# USB_hub.net
KiCad netlist of a schematic drawn in Altium Designer
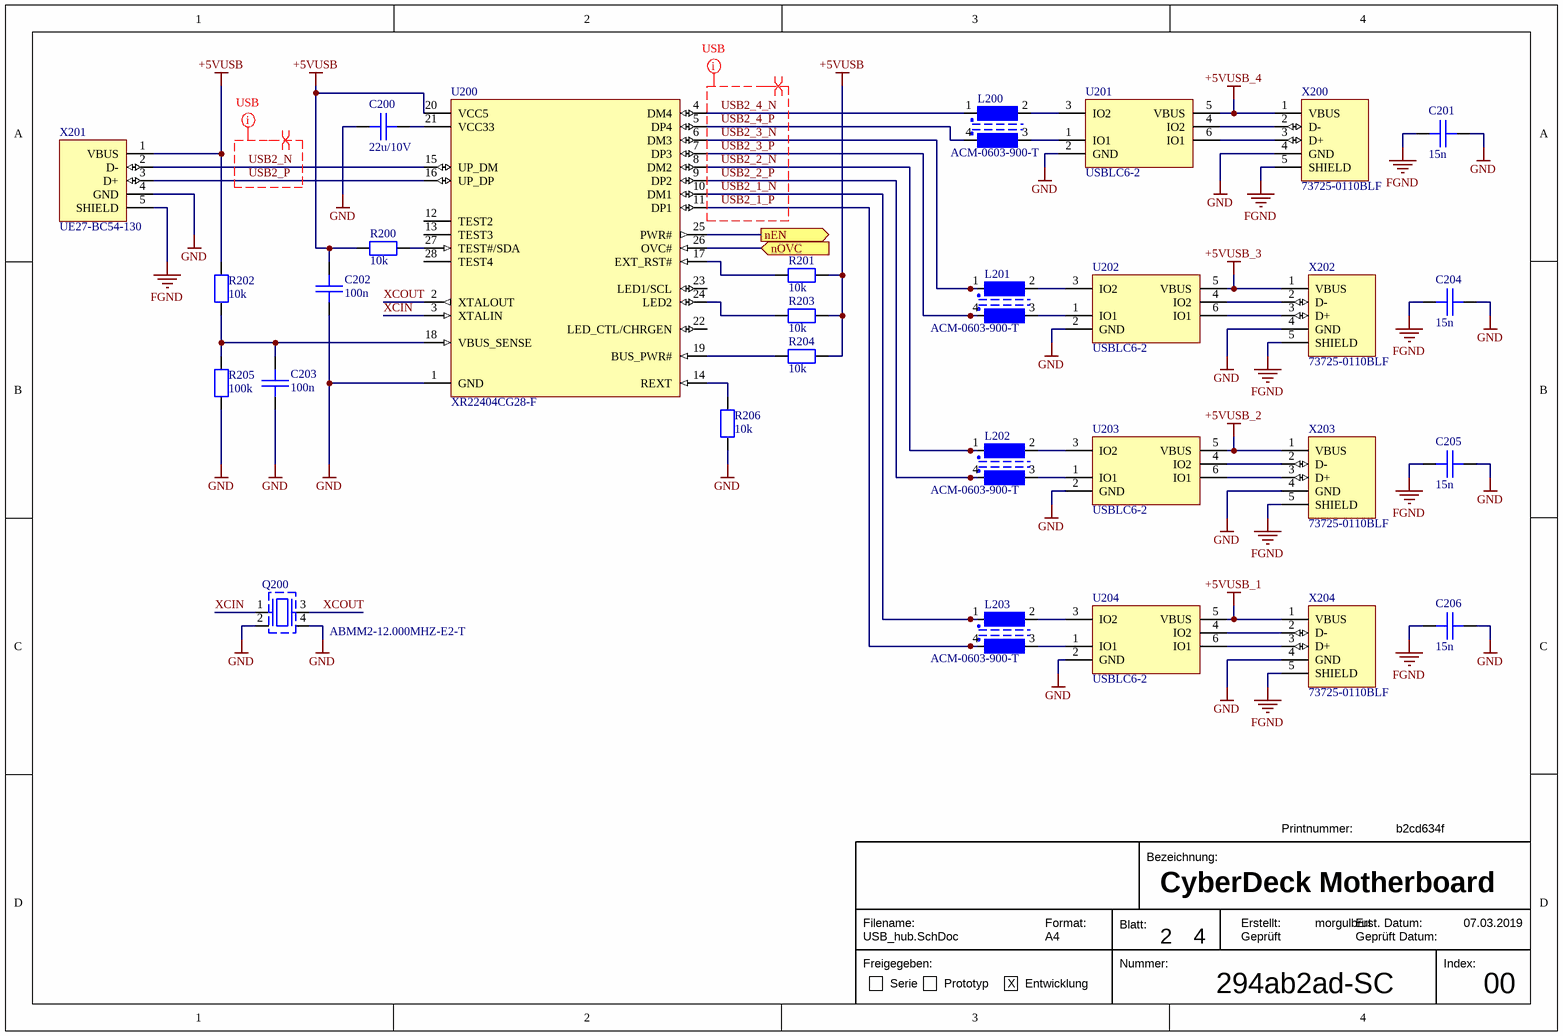
[diagram p0: USB_hub.SchDoc]

(export (version "E")
  (design (tool "Eeschema 10.0.6"))
  (components
    (comp (ref "C200")
      (value "22u/10V")
      (footprint "0805_C_E0")
      (description "Chip capacitor, generic")
      (libsource (lib "CyberDeck") (part "C"))
    )
    (comp (ref "C201")
      (value "15n")
      (footprint "0603_C")
      (description "Chip capacitor, generic")
      (libsource (lib "CyberDeck") (part "C"))
    )
    (comp (ref "C202")
      (value "100n")
      (footprint "0603_C")
      (description "Chip capacitor, generic")
      (libsource (lib "CyberDeck") (part "C"))
    )
    (comp (ref "C203")
      (value "100n")
      (footprint "0603_C")
      (description "Chip capacitor, generic")
      (libsource (lib "CyberDeck") (part "C"))
    )
    (comp (ref "C204")
      (value "15n")
      (footprint "0603_C")
      (description "Chip capacitor, generic")
      (libsource (lib "CyberDeck") (part "C"))
    )
    (comp (ref "C205")
      (value "15n")
      (footprint "0603_C")
      (description "Chip capacitor, generic")
      (libsource (lib "CyberDeck") (part "C"))
    )
    (comp (ref "C206")
      (value "15n")
      (footprint "0603_C")
      (description "Chip capacitor, generic")
      (libsource (lib "CyberDeck") (part "C"))
    )
    (comp (ref "L200")
      (value "ACM-0603-900-T")
      (footprint "ACM-0603-900-T")
      (description "INDUCTOR COMMON MODE SMD")
      (fields (field (name "MANUFACTURER") "Abracon"))
      (libsource (lib "CyberDeck") (part "L_ACM-0603-900-T"))
    )
    (comp (ref "L201")
      (value "ACM-0603-900-T")
      (footprint "ACM-0603-900-T")
      (description "INDUCTOR COMMON MODE SMD")
      (fields (field (name "MANUFACTURER") "Abracon"))
      (libsource (lib "CyberDeck") (part "L_ACM-0603-900-T"))
    )
    (comp (ref "L202")
      (value "ACM-0603-900-T")
      (footprint "ACM-0603-900-T")
      (description "INDUCTOR COMMON MODE SMD")
      (fields (field (name "MANUFACTURER") "Abracon"))
      (libsource (lib "CyberDeck") (part "L_ACM-0603-900-T"))
    )
    (comp (ref "L203")
      (value "ACM-0603-900-T")
      (footprint "ACM-0603-900-T")
      (description "INDUCTOR COMMON MODE SMD")
      (fields (field (name "MANUFACTURER") "Abracon"))
      (libsource (lib "CyberDeck") (part "L_ACM-0603-900-T"))
    )
    (comp (ref "Q200")
      (value "ABMM2-12.000MHZ-E2-T")
      (footprint "ABMM2")
      (description "12MHz ±20ppm Crystal 18pF 50 Ohm -20°C ~ 70°C  Surface Mount 4-SMD, No Lead (DFN, LCC)")
      (fields (field (name "MANUFACTURER") "Abracon"))
      (libsource (lib "CyberDeck") (part "Q_ABMM2-12.000MHZ-E2-T"))
    )
    (comp (ref "R200")
      (value "10k")
      (footprint "0805_R")
      (description "Resistor, generic")
      (libsource (lib "CyberDeck") (part "R"))
    )
    (comp (ref "R201")
      (value "10k")
      (footprint "0805_R")
      (description "Resistor, generic")
      (libsource (lib "") (part "R_1"))
    )
    (comp (ref "R202")
      (value "10k")
      (footprint "0805_R")
      (description "Resistor, generic")
      (libsource (lib "") (part "R_2"))
    )
    (comp (ref "R203")
      (value "10k")
      (footprint "0805_R")
      (description "Resistor, generic")
      (libsource (lib "") (part "R_1"))
    )
    (comp (ref "R204")
      (value "10k")
      (footprint "0805_R")
      (description "Resistor, generic")
      (libsource (lib "CyberDeck") (part "R"))
    )
    (comp (ref "R205")
      (value "100k")
      (footprint "0805_R")
      (description "Resistor, generic")
      (libsource (lib "") (part "R_2"))
    )
    (comp (ref "R206")
      (value "10k")
      (footprint "0805_R")
      (description "Resistor, generic")
      (libsource (lib "") (part "R_3"))
    )
    (comp (ref "U200")
      (value "XR22404CG28-F")
      (footprint "SSOP-28")
      (description "USB Controller USB 2.0 USB Interface")
      (fields (field (name "MANUFACTURER") "Exar"))
      (libsource (lib "CyberDeck") (part "U_T_XR22404CG28-F"))
    )
    (comp (ref "U201")
      (value "USBLC6-2")
      (footprint "SOT-666")
      (description "TVS DIODE 5.25VWM 17VC SOT666")
      (fields
        (field (name "MANUFACTURER") "STMicroelectronics")
        (field (name "MANUFACTURER PART NUMBER") "USBLC6-2P6")
      )
      (libsource (lib "CyberDeck") (part "D_USBLC6-2"))
    )
    (comp (ref "U202")
      (value "USBLC6-2")
      (footprint "SOT-666")
      (description "TVS DIODE 5.25VWM 17VC SOT666")
      (fields
        (field (name "MANUFACTURER") "STMicroelectronics")
        (field (name "MANUFACTURER PART NUMBER") "USBLC6-2P6")
      )
      (libsource (lib "CyberDeck") (part "D_USBLC6-2"))
    )
    (comp (ref "U203")
      (value "USBLC6-2")
      (footprint "SOT-666")
      (description "TVS DIODE 5.25VWM 17VC SOT666")
      (fields
        (field (name "MANUFACTURER") "STMicroelectronics")
        (field (name "MANUFACTURER PART NUMBER") "USBLC6-2P6")
      )
      (libsource (lib "CyberDeck") (part "D_USBLC6-2"))
    )
    (comp (ref "U204")
      (value "USBLC6-2")
      (footprint "SOT-666")
      (description "TVS DIODE 5.25VWM 17VC SOT666")
      (fields
        (field (name "MANUFACTURER") "STMicroelectronics")
        (field (name "MANUFACTURER PART NUMBER") "USBLC6-2P6")
      )
      (libsource (lib "CyberDeck") (part "D_USBLC6-2"))
    )
    (comp (ref "X200")
      (value "73725-0110BLF")
      (footprint "73725-0110BLF")
      (description "CONN RCPT USB2.0 TYPEA 4POS R/A")
      (libsource (lib "CyberDeck") (part "X_73725-0110BLF"))
    )
    (comp (ref "X201")
      (value "UE27-BC54-130")
      (footprint "UE27BC54130")
      (description "USB Connectors 4P PCB R/A TYPE B BLACK W/ REAR SHIELD")
      (libsource (lib "CyberDeck") (part "X_UE27-BC54-130"))
    )
    (comp (ref "X202")
      (value "73725-0110BLF")
      (footprint "73725-0110BLF")
      (description "CONN RCPT USB2.0 TYPEA 4POS R/A")
      (libsource (lib "CyberDeck") (part "X_73725-0110BLF"))
    )
    (comp (ref "X203")
      (value "73725-0110BLF")
      (footprint "73725-0110BLF")
      (description "CONN RCPT USB2.0 TYPEA 4POS R/A")
      (libsource (lib "CyberDeck") (part "X_73725-0110BLF"))
    )
    (comp (ref "X204")
      (value "73725-0110BLF")
      (footprint "73725-0110BLF")
      (description "CONN RCPT USB2.0 TYPEA 4POS R/A")
      (libsource (lib "CyberDeck") (part "X_73725-0110BLF"))
    )
  )
  (nets
    (net (code "1") (name "+5VUSB") (class "Default")
      (node (ref "C202") (pin "2") (pinfunction "2_2") (pintype "passive"))
      (node (ref "R200") (pin "2") (pinfunction "2_2") (pintype "passive"))
      (node (ref "R201") (pin "2") (pinfunction "2_2") (pintype "passive"))
      (node (ref "R202") (pin "2") (pinfunction "2_2") (pintype "passive"))
      (node (ref "R203") (pin "2") (pinfunction "2_2") (pintype "passive"))
      (node (ref "R204") (pin "1") (pinfunction "1_1") (pintype "passive"))
      (node (ref "U200") (pin "20") (pinfunction "VCC5_20") (pintype "power_in"))
      (node (ref "X201") (pin "1") (pinfunction "VBUS_1") (pintype "power_in"))
    )
    (net (code "2") (name "+5VUSB_1") (class "Default")
      (node (ref "U204") (pin "5") (pinfunction "VBUS_5") (pintype "passive"))
      (node (ref "X204") (pin "1") (pinfunction "VBUS_1") (pintype "power_in"))
    )
    (net (code "3") (name "+5VUSB_2") (class "Default")
      (node (ref "U203") (pin "5") (pinfunction "VBUS_5") (pintype "passive"))
      (node (ref "X203") (pin "1") (pinfunction "VBUS_1") (pintype "power_in"))
    )
    (net (code "4") (name "+5VUSB_3") (class "Default")
      (node (ref "U202") (pin "5") (pinfunction "VBUS_5") (pintype "passive"))
      (node (ref "X202") (pin "1") (pinfunction "VBUS_1") (pintype "power_in"))
    )
    (net (code "5") (name "+5VUSB_4") (class "Default")
      (node (ref "U201") (pin "5") (pinfunction "VBUS_5") (pintype "passive"))
      (node (ref "X200") (pin "1") (pinfunction "VBUS_1") (pintype "power_in"))
    )
    (net (code "6") (name "/USB2_1_N") (class "Default")
      (node (ref "L203") (pin "1") (pinfunction "1_1") (pintype "passive"))
      (node (ref "U200") (pin "10") (pinfunction "DM1_10") (pintype "bidirectional"))
    )
    (net (code "7") (name "/USB2_1_P") (class "Default")
      (node (ref "L203") (pin "4") (pinfunction "4_4") (pintype "passive"))
      (node (ref "U200") (pin "11") (pinfunction "DP1_11") (pintype "bidirectional"))
    )
    (net (code "8") (name "/USB2_2_N") (class "Default")
      (node (ref "L202") (pin "1") (pinfunction "1_1") (pintype "passive"))
      (node (ref "U200") (pin "8") (pinfunction "DM2_8") (pintype "bidirectional"))
    )
    (net (code "9") (name "/USB2_2_P") (class "Default")
      (node (ref "L202") (pin "4") (pinfunction "4_4") (pintype "passive"))
      (node (ref "U200") (pin "9") (pinfunction "DP2_9") (pintype "bidirectional"))
    )
    (net (code "10") (name "/USB2_3_N") (class "Default")
      (node (ref "L201") (pin "1") (pinfunction "1_1") (pintype "passive"))
      (node (ref "U200") (pin "6") (pinfunction "DM3_6") (pintype "bidirectional"))
    )
    (net (code "11") (name "/USB2_3_P") (class "Default")
      (node (ref "L201") (pin "4") (pinfunction "4_4") (pintype "passive"))
      (node (ref "U200") (pin "7") (pinfunction "DP3_7") (pintype "bidirectional"))
    )
    (net (code "12") (name "/USB2_4_N") (class "Default")
      (node (ref "L200") (pin "1") (pinfunction "1_1") (pintype "passive"))
      (node (ref "U200") (pin "4") (pinfunction "DM4_4") (pintype "bidirectional"))
    )
    (net (code "13") (name "/USB2_4_P") (class "Default")
      (node (ref "L200") (pin "4") (pinfunction "4_4") (pintype "passive"))
      (node (ref "U200") (pin "5") (pinfunction "DP4_5") (pintype "bidirectional"))
    )
    (net (code "14") (name "/USB2_N") (class "Default")
      (node (ref "U200") (pin "15") (pinfunction "UP_DM_15") (pintype "bidirectional"))
      (node (ref "X201") (pin "2") (pinfunction "D-_2") (pintype "bidirectional"))
    )
    (net (code "15") (name "/USB2_P") (class "Default")
      (node (ref "U200") (pin "16") (pinfunction "UP_DP_16") (pintype "bidirectional"))
      (node (ref "X201") (pin "3") (pinfunction "D+_3") (pintype "bidirectional"))
    )
    (net (code "16") (name "/XCIN") (class "Default")
      (node (ref "Q200") (pin "1") (pinfunction "1_1") (pintype "passive"))
      (node (ref "U200") (pin "3") (pinfunction "XTALIN_3") (pintype "input"))
    )
    (net (code "17") (name "/XCOUT") (class "Default")
      (node (ref "Q200") (pin "3") (pinfunction "3_3") (pintype "passive"))
      (node (ref "U200") (pin "2") (pinfunction "XTALOUT_2") (pintype "output"))
    )
    (net (code "18") (name "/nEN") (class "Default")
      (node (ref "U200") (pin "25") (pinfunction "PWR#_25") (pintype "output"))
    )
    (net (code "19") (name "/nOVC") (class "Default")
      (node (ref "U200") (pin "26") (pinfunction "OVC#_26") (pintype "input"))
    )
    (net (code "20") (name "FGND") (class "Default")
      (node (ref "C201") (pin "1") (pinfunction "1_1") (pintype "passive"))
      (node (ref "C204") (pin "1") (pinfunction "1_1") (pintype "passive"))
      (node (ref "C205") (pin "1") (pinfunction "1_1") (pintype "passive"))
      (node (ref "C206") (pin "1") (pinfunction "1_1") (pintype "passive"))
      (node (ref "X200") (pin "5") (pinfunction "SHIELD_5") (pintype "power_in"))
      (node (ref "X201") (pin "5") (pinfunction "SHIELD_5") (pintype "power_in"))
      (node (ref "X202") (pin "5") (pinfunction "SHIELD_5") (pintype "power_in"))
      (node (ref "X203") (pin "5") (pinfunction "SHIELD_5") (pintype "power_in"))
      (node (ref "X204") (pin "5") (pinfunction "SHIELD_5") (pintype "power_in"))
    )
    (net (code "21") (name "GND") (class "Default")
      (node (ref "C200") (pin "2") (pinfunction "2_2") (pintype "passive"))
      (node (ref "C201") (pin "2") (pinfunction "2_2") (pintype "passive"))
      (node (ref "C202") (pin "1") (pinfunction "1_1") (pintype "passive"))
      (node (ref "C203") (pin "1") (pinfunction "1_1") (pintype "passive"))
      (node (ref "C204") (pin "2") (pinfunction "2_2") (pintype "passive"))
      (node (ref "C205") (pin "2") (pinfunction "2_2") (pintype "passive"))
      (node (ref "C206") (pin "2") (pinfunction "2_2") (pintype "passive"))
      (node (ref "Q200") (pin "2") (pinfunction "2_2") (pintype "passive"))
      (node (ref "Q200") (pin "4") (pinfunction "3_4") (pintype "passive"))
      (node (ref "R205") (pin "1") (pinfunction "1_1") (pintype "passive"))
      (node (ref "R206") (pin "2") (pinfunction "2_2") (pintype "passive"))
      (node (ref "U200") (pin "1") (pinfunction "GND_1") (pintype "power_in"))
      (node (ref "U201") (pin "2") (pinfunction "GND_2") (pintype "passive"))
      (node (ref "U202") (pin "2") (pinfunction "GND_2") (pintype "passive"))
      (node (ref "U203") (pin "2") (pinfunction "GND_2") (pintype "passive"))
      (node (ref "U204") (pin "2") (pinfunction "GND_2") (pintype "passive"))
      (node (ref "X200") (pin "4") (pinfunction "GND_4") (pintype "power_in"))
      (node (ref "X201") (pin "4") (pinfunction "GND_4") (pintype "power_in"))
      (node (ref "X202") (pin "4") (pinfunction "GND_4") (pintype "power_in"))
      (node (ref "X203") (pin "4") (pinfunction "GND_4") (pintype "power_in"))
      (node (ref "X204") (pin "4") (pinfunction "GND_4") (pintype "power_in"))
    )
    (net (code "22") (name "Net-(L200-Pad2)") (class "Default")
      (node (ref "L200") (pin "2") (pinfunction "2_2") (pintype "passive"))
      (node (ref "U201") (pin "3") (pinfunction "IO2_3") (pintype "passive"))
    )
    (net (code "23") (name "Net-(L200-Pad3)") (class "Default")
      (node (ref "L200") (pin "3") (pinfunction "3_3") (pintype "passive"))
      (node (ref "U201") (pin "1") (pinfunction "IO1_1") (pintype "passive"))
    )
    (net (code "24") (name "Net-(L201-Pad2)") (class "Default")
      (node (ref "L201") (pin "2") (pinfunction "2_2") (pintype "passive"))
      (node (ref "U202") (pin "3") (pinfunction "IO2_3") (pintype "passive"))
    )
    (net (code "25") (name "Net-(L201-Pad3)") (class "Default")
      (node (ref "L201") (pin "3") (pinfunction "3_3") (pintype "passive"))
      (node (ref "U202") (pin "1") (pinfunction "IO1_1") (pintype "passive"))
    )
    (net (code "26") (name "Net-(L202-Pad2)") (class "Default")
      (node (ref "L202") (pin "2") (pinfunction "2_2") (pintype "passive"))
      (node (ref "U203") (pin "3") (pinfunction "IO2_3") (pintype "passive"))
    )
    (net (code "27") (name "Net-(L202-Pad3)") (class "Default")
      (node (ref "L202") (pin "3") (pinfunction "3_3") (pintype "passive"))
      (node (ref "U203") (pin "1") (pinfunction "IO1_1") (pintype "passive"))
    )
    (net (code "28") (name "Net-(L203-Pad2)") (class "Default")
      (node (ref "L203") (pin "2") (pinfunction "2_2") (pintype "passive"))
      (node (ref "U204") (pin "3") (pinfunction "IO2_3") (pintype "passive"))
    )
    (net (code "29") (name "Net-(L203-Pad3)") (class "Default")
      (node (ref "L203") (pin "3") (pinfunction "3_3") (pintype "passive"))
      (node (ref "U204") (pin "1") (pinfunction "IO1_1") (pintype "passive"))
    )
    (net (code "30") (name "Net-(U200-BUS_PWR#)") (class "Default")
      (node (ref "R204") (pin "2") (pinfunction "2_2") (pintype "passive"))
      (node (ref "U200") (pin "19") (pinfunction "BUS_PWR#_19") (pintype "input"))
    )
    (net (code "31") (name "Net-(U200-EXT_RST#)") (class "Default")
      (node (ref "R201") (pin "1") (pinfunction "1_1") (pintype "passive"))
      (node (ref "U200") (pin "17") (pinfunction "EXT_RST#_17") (pintype "input"))
    )
    (net (code "32") (name "Net-(U200-LED2)") (class "Default")
      (node (ref "R203") (pin "1") (pinfunction "1_1") (pintype "passive"))
      (node (ref "U200") (pin "24") (pinfunction "LED2_24") (pintype "bidirectional"))
    )
    (net (code "33") (name "Net-(U200-REXT)") (class "Default")
      (node (ref "R206") (pin "1") (pinfunction "1_1") (pintype "passive"))
      (node (ref "U200") (pin "14") (pinfunction "REXT_14") (pintype "input"))
    )
    (net (code "34") (name "Net-(U200-TEST#{slash}SDA)") (class "Default")
      (node (ref "R200") (pin "1") (pinfunction "1_1") (pintype "passive"))
      (node (ref "U200") (pin "27") (pinfunction "TEST#/SDA_27") (pintype "input"))
    )
    (net (code "35") (name "Net-(U200-VBUS_SENSE)") (class "Default")
      (node (ref "C203") (pin "2") (pinfunction "2_2") (pintype "passive"))
      (node (ref "R202") (pin "1") (pinfunction "1_1") (pintype "passive"))
      (node (ref "R205") (pin "2") (pinfunction "2_2") (pintype "passive"))
      (node (ref "U200") (pin "18") (pinfunction "VBUS_SENSE_18") (pintype "input"))
    )
    (net (code "36") (name "Net-(U200-VCC33)") (class "Default")
      (node (ref "C200") (pin "1") (pinfunction "1_1") (pintype "passive"))
      (node (ref "U200") (pin "21") (pinfunction "VCC33_21") (pintype "power_in"))
    )
    (net (code "37") (name "Net-(X200-D+)") (class "Default")
      (node (ref "U201") (pin "6") (pinfunction "IO1_6") (pintype "passive"))
      (node (ref "X200") (pin "3") (pinfunction "D+_3") (pintype "bidirectional"))
    )
    (net (code "38") (name "Net-(X200-D-)") (class "Default")
      (node (ref "U201") (pin "4") (pinfunction "IO2_4") (pintype "passive"))
      (node (ref "X200") (pin "2") (pinfunction "D-_2") (pintype "bidirectional"))
    )
    (net (code "39") (name "Net-(X202-D+)") (class "Default")
      (node (ref "U202") (pin "6") (pinfunction "IO1_6") (pintype "passive"))
      (node (ref "X202") (pin "3") (pinfunction "D+_3") (pintype "bidirectional"))
    )
    (net (code "40") (name "Net-(X202-D-)") (class "Default")
      (node (ref "U202") (pin "4") (pinfunction "IO2_4") (pintype "passive"))
      (node (ref "X202") (pin "2") (pinfunction "D-_2") (pintype "bidirectional"))
    )
    (net (code "41") (name "Net-(X203-D+)") (class "Default")
      (node (ref "U203") (pin "6") (pinfunction "IO1_6") (pintype "passive"))
      (node (ref "X203") (pin "3") (pinfunction "D+_3") (pintype "bidirectional"))
    )
    (net (code "42") (name "Net-(X203-D-)") (class "Default")
      (node (ref "U203") (pin "4") (pinfunction "IO2_4") (pintype "passive"))
      (node (ref "X203") (pin "2") (pinfunction "D-_2") (pintype "bidirectional"))
    )
    (net (code "43") (name "Net-(X204-D+)") (class "Default")
      (node (ref "U204") (pin "6") (pinfunction "IO1_6") (pintype "passive"))
      (node (ref "X204") (pin "3") (pinfunction "D+_3") (pintype "bidirectional"))
    )
    (net (code "44") (name "Net-(X204-D-)") (class "Default")
      (node (ref "U204") (pin "4") (pinfunction "IO2_4") (pintype "passive"))
      (node (ref "X204") (pin "2") (pinfunction "D-_2") (pintype "bidirectional"))
    )
    (net (code "45") (name "unconnected-(U200-LED1{slash}SCL-Pad23)") (class "Default")
      (node (ref "U200") (pin "23") (pinfunction "LED1/SCL_23") (pintype "bidirectional"))
    )
    (net (code "46") (name "unconnected-(U200-LED_CTL{slash}CHRGEN-Pad22)") (class "Default")
      (node (ref "U200") (pin "22") (pinfunction "LED_CTL/CHRGEN_22") (pintype "bidirectional"))
    )
    (net (code "47") (name "unconnected-(U200-TEST2-Pad12)") (class "Default")
      (node (ref "U200") (pin "12") (pinfunction "TEST2_12") (pintype "passive"))
    )
    (net (code "48") (name "unconnected-(U200-TEST3-Pad13)") (class "Default")
      (node (ref "U200") (pin "13") (pinfunction "TEST3_13") (pintype "passive"))
    )
    (net (code "49") (name "unconnected-(U200-TEST4-Pad28)") (class "Default")
      (node (ref "U200") (pin "28") (pinfunction "TEST4_28") (pintype "passive"))
    )
  )
)
